# Offsetboard.net
KiCad netlist of a schematic drawn in EAGLE
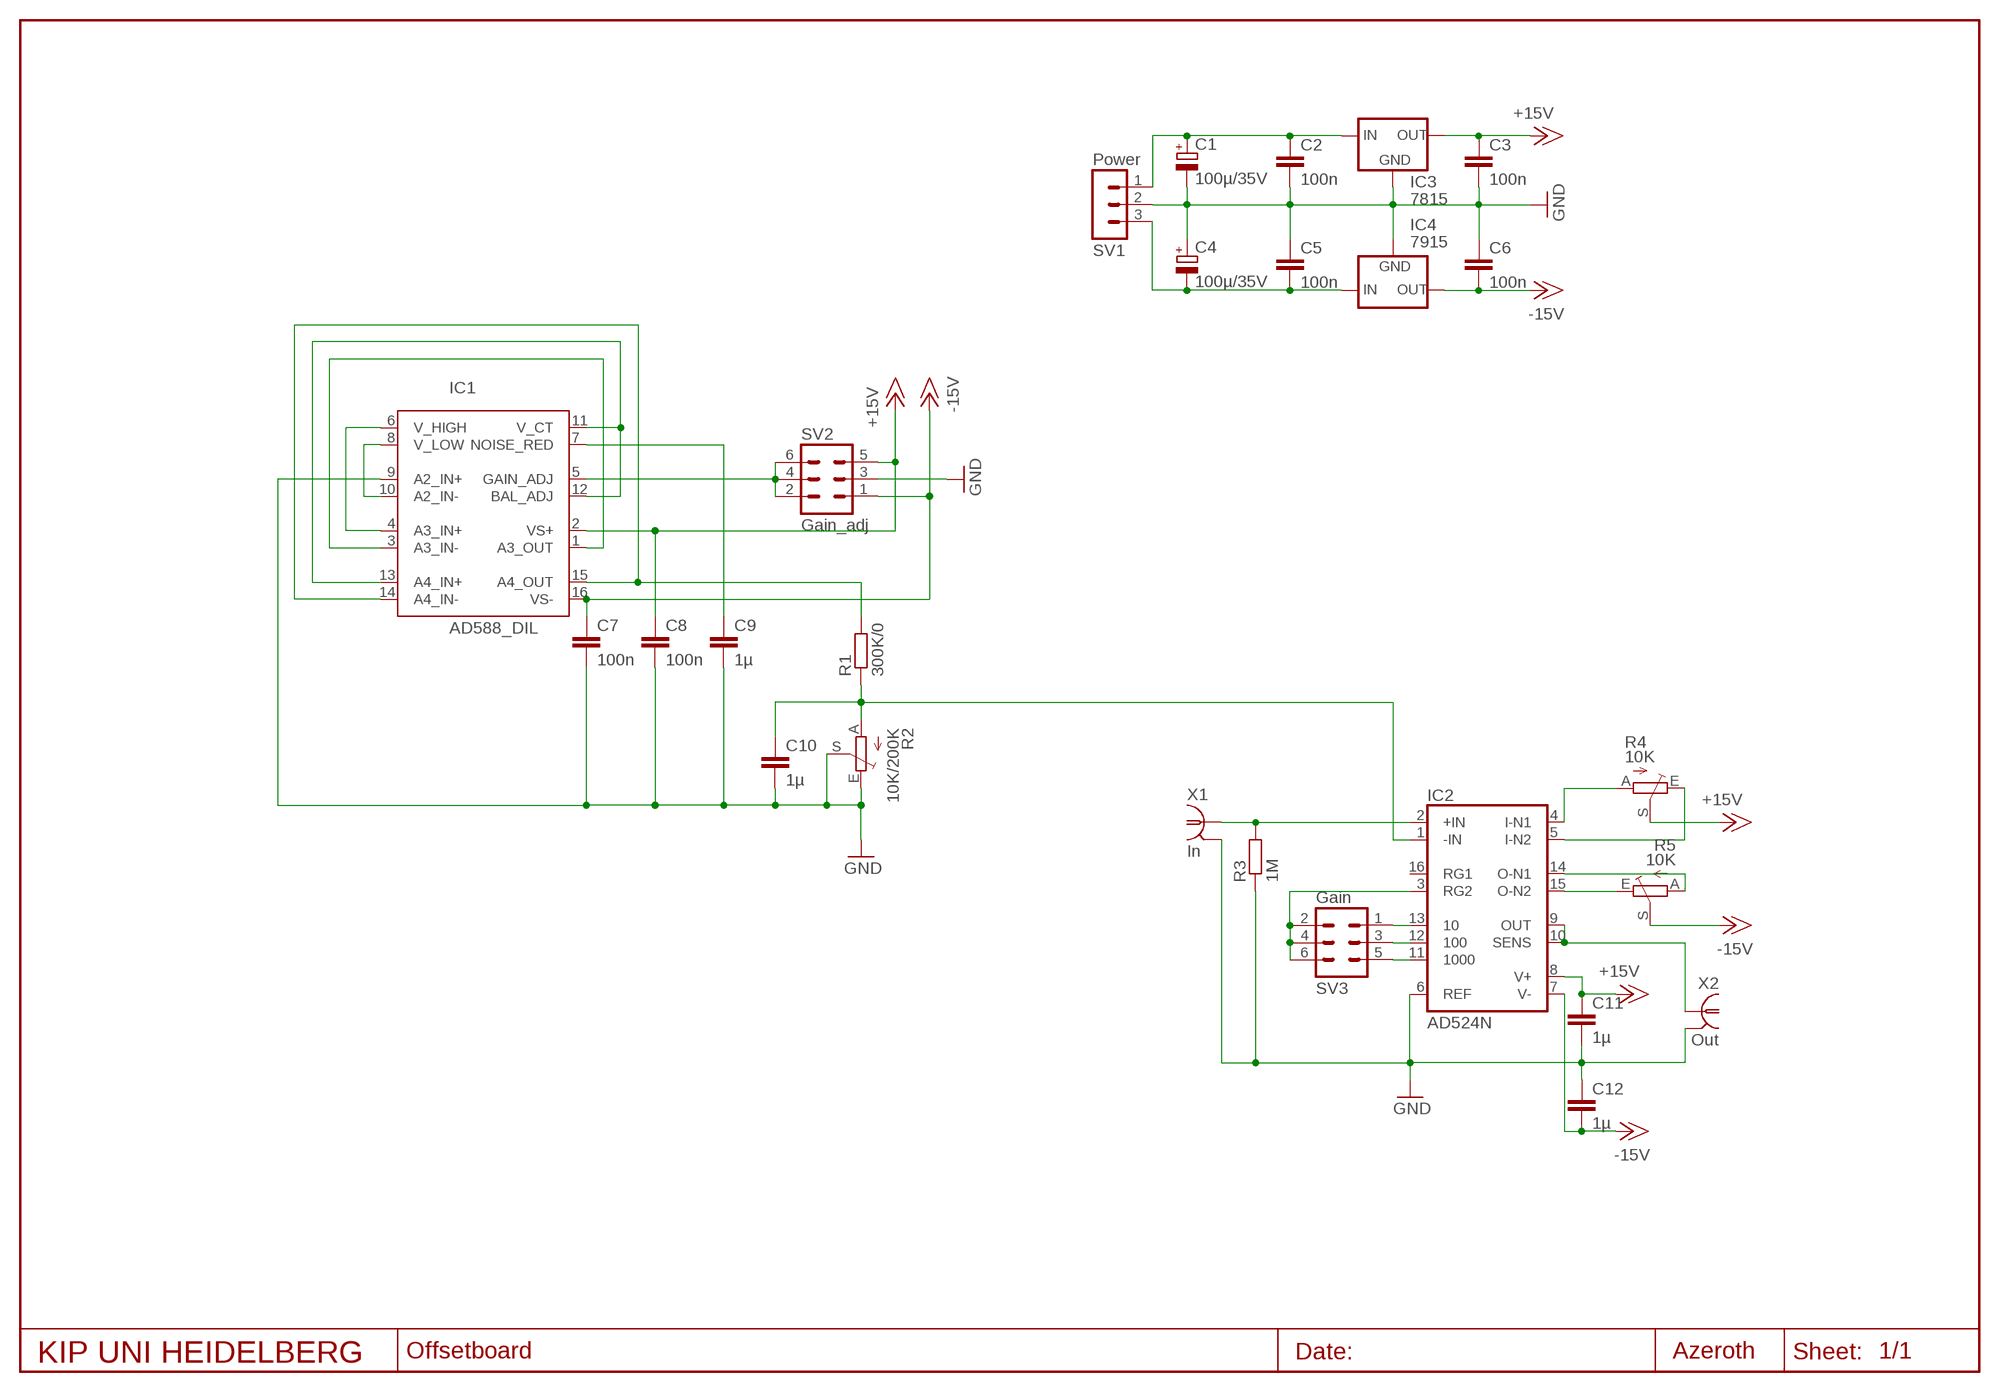
[diagram p0: schematic, sheet 1]

(export (version "E")
  (design (tool "Eeschema 10.0.6"))
  (components
    (comp (ref "C1")
      (value "100µ/35V")
      (footprint "eagle-import:E2,5-6")
      (libsource (lib "eagle-import") (part "CPOL-EUE2.5-6"))
    )
    (comp (ref "C2")
      (value "100n")
      (footprint "eagle-import:C1206K")
      (libsource (lib "eagle-import") (part "C-EUC1206K"))
    )
    (comp (ref "C3")
      (value "100n")
      (footprint "eagle-import:C1206K")
      (libsource (lib "eagle-import") (part "C-EUC1206K"))
    )
    (comp (ref "C4")
      (value "100µ/35V")
      (footprint "eagle-import:E2,5-6")
      (libsource (lib "eagle-import") (part "CPOL-EUE2.5-6"))
    )
    (comp (ref "C5")
      (value "100n")
      (footprint "eagle-import:C1206K")
      (libsource (lib "eagle-import") (part "C-EUC1206K"))
    )
    (comp (ref "C6")
      (value "100n")
      (footprint "eagle-import:C1206K")
      (libsource (lib "eagle-import") (part "C-EUC1206K"))
    )
    (comp (ref "C7")
      (value "100n")
      (footprint "eagle-import:C1206K")
      (libsource (lib "eagle-import") (part "C-EUC1206K"))
    )
    (comp (ref "C8")
      (value "100n")
      (footprint "eagle-import:C1206K")
      (libsource (lib "eagle-import") (part "C-EUC1206K"))
    )
    (comp (ref "C9")
      (value "1µ")
      (footprint "eagle-import:C1206K")
      (libsource (lib "eagle-import") (part "C-EUC1206K"))
    )
    (comp (ref "C10")
      (value "1µ")
      (footprint "eagle-import:C1206K")
      (libsource (lib "eagle-import") (part "C-EUC1206K"))
    )
    (comp (ref "C11")
      (value "1µ")
      (footprint "eagle-import:C1206K")
      (libsource (lib "eagle-import") (part "C-EUC1206K"))
    )
    (comp (ref "C12")
      (value "1µ")
      (footprint "eagle-import:C1206K")
      (libsource (lib "eagle-import") (part "C-EUC1206K"))
    )
    (comp (ref "IC1")
      (value "AD588_DIL")
      (footprint "eagle-import:DIL16")
      (libsource (lib "eagle-import") (part "AD588_DIL"))
    )
    (comp (ref "IC2")
      (value "AD524N")
      (footprint "eagle-import:DIL16")
      (libsource (lib "eagle-import") (part "AD524N"))
    )
    (comp (ref "IC3")
      (value "7815")
      (footprint "eagle-import:78MXXS")
      (libsource (lib "eagle-import") (part "78MXXS"))
    )
    (comp (ref "IC4")
      (value "7915")
      (footprint "eagle-import:79XXS")
      (libsource (lib "eagle-import") (part "79XXS"))
    )
    (comp (ref "R1")
      (value "300K/0")
      (footprint "eagle-import:0207_10")
      (libsource (lib "eagle-import") (part "R-EU_0207/10"))
    )
    (comp (ref "R2")
      (value "10K/200K")
      (footprint "eagle-import:S64W")
      (libsource (lib "eagle-import") (part "TRIM_EU-S64W"))
    )
    (comp (ref "R3")
      (value "1M")
      (footprint "eagle-import:0207_10")
      (libsource (lib "eagle-import") (part "R-EU_0207/10"))
    )
    (comp (ref "R4")
      (value "10K")
      (footprint "eagle-import:S64W")
      (libsource (lib "eagle-import") (part "TRIM_EU-S64W"))
    )
    (comp (ref "R5")
      (value "10K")
      (footprint "eagle-import:S64W")
      (libsource (lib "eagle-import") (part "TRIM_EU-S64W"))
    )
    (comp (ref "SV1")
      (value "Power")
      (footprint "eagle-import:MA03-1")
      (libsource (lib "eagle-import") (part "MA03-1"))
    )
    (comp (ref "SV2")
      (value "Gain_adj")
      (footprint "eagle-import:MA03-2")
      (libsource (lib "eagle-import") (part "MA03-2"))
    )
    (comp (ref "SV3")
      (value "Gain")
      (footprint "eagle-import:MA03-2")
      (libsource (lib "eagle-import") (part "MA03-2"))
    )
    (comp (ref "X1")
      (value "In")
      (footprint "eagle-import:AMP_227161")
      (fields (field (name "MF") "TYCO ELECTRONICS") (field (name "MPN") "1-227161"))
      (libsource (lib "eagle-import") (part "?2271611--0"))
    )
    (comp (ref "X2")
      (value "Out")
      (footprint "eagle-import:AMP_227161")
      (fields (field (name "MF") "TYCO ELECTRONICS") (field (name "MPN") "1-227161"))
      (libsource (lib "eagle-import") (part "?2271611--0"))
    )
  )
  (nets
    (net (code "1") (name "+15V") (class "Default")
      (node (ref "C11") (pin "1") (pinfunction "1_1") (pintype "passive"))
      (node (ref "C3") (pin "1") (pinfunction "1_1") (pintype "passive"))
      (node (ref "C8") (pin "1") (pinfunction "1_1") (pintype "passive"))
      (node (ref "IC1") (pin "2") (pinfunction "VS+_2") (pintype "power_in"))
      (node (ref "IC2") (pin "8") (pinfunction "V+_8") (pintype "power_in"))
      (node (ref "IC3") (pin "OUT") (pinfunction "OUT_OUT") (pintype "passive"))
      (node (ref "R4") (pin "S") (pinfunction "S_S") (pintype "passive"))
      (node (ref "SV2") (pin "5") (pinfunction "5_5") (pintype "passive"))
    )
    (net (code "2") (name "-15V") (class "Default")
      (node (ref "C12") (pin "2") (pinfunction "2_2") (pintype "passive"))
      (node (ref "C6") (pin "2") (pinfunction "2_2") (pintype "passive"))
      (node (ref "C7") (pin "1") (pinfunction "1_1") (pintype "passive"))
      (node (ref "IC1") (pin "16") (pinfunction "VS-_16") (pintype "power_in"))
      (node (ref "IC2") (pin "7") (pinfunction "V-_7") (pintype "power_in"))
      (node (ref "IC4") (pin "OUT") (pinfunction "OUT_OUT") (pintype "passive"))
      (node (ref "R5") (pin "S") (pinfunction "S_S") (pintype "passive"))
      (node (ref "SV2") (pin "1") (pinfunction "1_1") (pintype "passive"))
    )
    (net (code "3") (name "GND") (class "Default")
      (node (ref "C1") (pin "-") (pinfunction "-_-") (pintype "passive"))
      (node (ref "C10") (pin "2") (pinfunction "2_2") (pintype "passive"))
      (node (ref "C11") (pin "2") (pinfunction "2_2") (pintype "passive"))
      (node (ref "C12") (pin "1") (pinfunction "1_1") (pintype "passive"))
      (node (ref "C2") (pin "2") (pinfunction "2_2") (pintype "passive"))
      (node (ref "C3") (pin "2") (pinfunction "2_2") (pintype "passive"))
      (node (ref "C4") (pin "+") (pinfunction "+_+") (pintype "passive"))
      (node (ref "C5") (pin "1") (pinfunction "1_1") (pintype "passive"))
      (node (ref "C6") (pin "1") (pinfunction "1_1") (pintype "passive"))
      (node (ref "C7") (pin "2") (pinfunction "2_2") (pintype "passive"))
      (node (ref "C8") (pin "2") (pinfunction "2_2") (pintype "passive"))
      (node (ref "C9") (pin "2") (pinfunction "2_2") (pintype "passive"))
      (node (ref "IC1") (pin "9") (pinfunction "A2_IN+_9") (pintype "bidirectional"))
      (node (ref "IC2") (pin "6") (pinfunction "REF_6") (pintype "input"))
      (node (ref "IC3") (pin "GND") (pinfunction "GND_GND") (pintype "input"))
      (node (ref "IC4") (pin "GND") (pinfunction "GND_GND") (pintype "input"))
      (node (ref "R2") (pin "E") (pinfunction "E_E") (pintype "passive"))
      (node (ref "R2") (pin "S") (pinfunction "S_S") (pintype "passive"))
      (node (ref "R3") (pin "1") (pinfunction "1_1") (pintype "passive"))
      (node (ref "SV1") (pin "2") (pinfunction "2_2") (pintype "passive"))
      (node (ref "SV2") (pin "3") (pinfunction "3_3") (pintype "passive"))
      (node (ref "X1") (pin "2") (pinfunction "GND_2") (pintype "power_in"))
      (node (ref "X2") (pin "2") (pinfunction "GND_2") (pintype "power_in"))
    )
    (net (code "4") (name "Net-(C1-Pad+)") (class "Default")
      (node (ref "C1") (pin "+") (pinfunction "+_+") (pintype "passive"))
      (node (ref "C2") (pin "1") (pinfunction "1_1") (pintype "passive"))
      (node (ref "IC3") (pin "IN") (pinfunction "IN_IN") (pintype "input"))
      (node (ref "SV1") (pin "1") (pinfunction "1_1") (pintype "passive"))
    )
    (net (code "5") (name "Net-(C4-Pad-)") (class "Default")
      (node (ref "C4") (pin "-") (pinfunction "-_-") (pintype "passive"))
      (node (ref "C5") (pin "2") (pinfunction "2_2") (pintype "passive"))
      (node (ref "IC4") (pin "IN") (pinfunction "IN_IN") (pintype "input"))
      (node (ref "SV1") (pin "3") (pinfunction "3_3") (pintype "passive"))
    )
    (net (code "6") (name "Net-(IC1-A2_IN-)") (class "Default")
      (node (ref "IC1") (pin "10") (pinfunction "A2_IN-_10") (pintype "bidirectional"))
      (node (ref "IC1") (pin "8") (pinfunction "V_LOW_8") (pintype "bidirectional"))
    )
    (net (code "7") (name "Net-(IC1-A3_IN+)") (class "Default")
      (node (ref "IC1") (pin "4") (pinfunction "A3_IN+_4") (pintype "bidirectional"))
      (node (ref "IC1") (pin "6") (pinfunction "V_HIGH_6") (pintype "bidirectional"))
    )
    (net (code "8") (name "Net-(IC1-A3_IN-)") (class "Default")
      (node (ref "IC1") (pin "1") (pinfunction "A3_OUT_1") (pintype "bidirectional"))
      (node (ref "IC1") (pin "3") (pinfunction "A3_IN-_3") (pintype "bidirectional"))
    )
    (net (code "9") (name "Net-(IC1-A4_IN+)") (class "Default")
      (node (ref "IC1") (pin "11") (pinfunction "V_CT_11") (pintype "bidirectional"))
      (node (ref "IC1") (pin "12") (pinfunction "BAL_ADJ_12") (pintype "bidirectional"))
      (node (ref "IC1") (pin "13") (pinfunction "A4_IN+_13") (pintype "bidirectional"))
    )
    (net (code "10") (name "Net-(IC1-A4_IN-)") (class "Default")
      (node (ref "IC1") (pin "14") (pinfunction "A4_IN-_14") (pintype "bidirectional"))
      (node (ref "IC1") (pin "15") (pinfunction "A4_OUT_15") (pintype "bidirectional"))
      (node (ref "R1") (pin "2") (pinfunction "2_2") (pintype "passive"))
    )
    (net (code "11") (name "Net-(IC1-GAIN_ADJ)") (class "Default")
      (node (ref "IC1") (pin "5") (pinfunction "GAIN_ADJ_5") (pintype "bidirectional"))
      (node (ref "SV2") (pin "2") (pinfunction "2_2") (pintype "passive"))
      (node (ref "SV2") (pin "4") (pinfunction "4_4") (pintype "passive"))
      (node (ref "SV2") (pin "6") (pinfunction "6_6") (pintype "passive"))
    )
    (net (code "12") (name "Net-(IC1-NOISE_RED)") (class "Default")
      (node (ref "C9") (pin "1") (pinfunction "1_1") (pintype "passive"))
      (node (ref "IC1") (pin "7") (pinfunction "NOISE_RED_7") (pintype "bidirectional"))
    )
    (net (code "13") (name "Net-(IC2-+IN)") (class "Default")
      (node (ref "IC2") (pin "2") (pinfunction "+IN_2") (pintype "input"))
      (node (ref "R3") (pin "2") (pinfunction "2_2") (pintype "passive"))
      (node (ref "X1") (pin "1") (pinfunction "1_1") (pintype "passive"))
    )
    (net (code "14") (name "Net-(IC2--IN)") (class "Default")
      (node (ref "C10") (pin "1") (pinfunction "1_1") (pintype "passive"))
      (node (ref "IC2") (pin "1") (pinfunction "-IN_1") (pintype "input"))
      (node (ref "R1") (pin "1") (pinfunction "1_1") (pintype "passive"))
      (node (ref "R2") (pin "A") (pinfunction "A_A") (pintype "passive"))
    )
    (net (code "15") (name "Net-(IC2-10)") (class "Default")
      (node (ref "IC2") (pin "13") (pinfunction "10_13") (pintype "output"))
      (node (ref "SV3") (pin "1") (pinfunction "1_1") (pintype "passive"))
    )
    (net (code "16") (name "Net-(IC2-100)") (class "Default")
      (node (ref "IC2") (pin "12") (pinfunction "100_12") (pintype "output"))
      (node (ref "SV3") (pin "3") (pinfunction "3_3") (pintype "passive"))
    )
    (net (code "17") (name "Net-(IC2-1000)") (class "Default")
      (node (ref "IC2") (pin "11") (pinfunction "1000_11") (pintype "output"))
      (node (ref "SV3") (pin "5") (pinfunction "5_5") (pintype "passive"))
    )
    (net (code "18") (name "Net-(IC2-I-N1)") (class "Default")
      (node (ref "IC2") (pin "4") (pinfunction "I-N1_4") (pintype "input"))
      (node (ref "R4") (pin "A") (pinfunction "A_A") (pintype "passive"))
    )
    (net (code "19") (name "Net-(IC2-I-N2)") (class "Default")
      (node (ref "IC2") (pin "5") (pinfunction "I-N2_5") (pintype "input"))
      (node (ref "R4") (pin "E") (pinfunction "E_E") (pintype "passive"))
    )
    (net (code "20") (name "Net-(IC2-O-N1)") (class "Default")
      (node (ref "IC2") (pin "14") (pinfunction "O-N1_14") (pintype "input"))
      (node (ref "R5") (pin "A") (pinfunction "A_A") (pintype "passive"))
    )
    (net (code "21") (name "Net-(IC2-O-N2)") (class "Default")
      (node (ref "IC2") (pin "15") (pinfunction "O-N2_15") (pintype "input"))
      (node (ref "R5") (pin "E") (pinfunction "E_E") (pintype "passive"))
    )
    (net (code "22") (name "Net-(IC2-OUT)") (class "Default")
      (node (ref "IC2") (pin "10") (pinfunction "SENS_10") (pintype "input"))
      (node (ref "IC2") (pin "9") (pinfunction "OUT_9") (pintype "output"))
      (node (ref "X2") (pin "1") (pinfunction "1_1") (pintype "passive"))
    )
    (net (code "23") (name "Net-(IC2-RG2)") (class "Default")
      (node (ref "IC2") (pin "3") (pinfunction "RG2_3") (pintype "passive"))
      (node (ref "SV3") (pin "2") (pinfunction "2_2") (pintype "passive"))
      (node (ref "SV3") (pin "4") (pinfunction "4_4") (pintype "passive"))
      (node (ref "SV3") (pin "6") (pinfunction "6_6") (pintype "passive"))
    )
    (net (code "24") (name "unconnected-(IC2-RG1-Pad16)") (class "Default")
      (node (ref "IC2") (pin "16") (pinfunction "RG1_16") (pintype "passive"))
    )
  )
)
